# Sheet1.net
KiCad netlist of a schematic drawn in Altium Designer
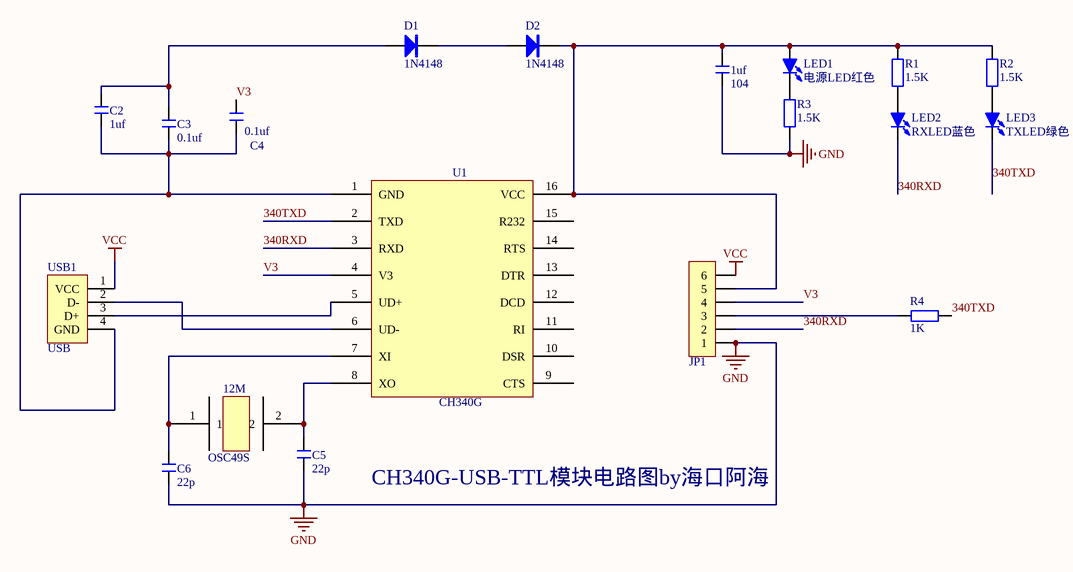
[diagram p0: Sheet1.SchDoc]

(export (version "E")
  (design (tool "Eeschema 10.0.6"))
  (components
    (comp (ref "1uf")
      (value "104")
      (footprint "C 0603_L")
      (description "贴片电容")
      (libsource (lib "0.1 - 电阻-电容-电感") (part "C"))
    )
    (comp (ref "12M")
      (value "OSC49S")
      (footprint "OSC HC-49S")
      (description "晶振49S")
      (libsource (lib "常用元件库") (part "OSC49S"))
    )
    (comp (ref "C2")
      (value "1uf")
      (footprint "C 0603_L")
      (description "贴片电容")
      (libsource (lib "0.1 - 电阻-电容-电感") (part "C"))
    )
    (comp (ref "C3")
      (value "0.1uf")
      (footprint "C 0603_L")
      (description "贴片电容")
      (libsource (lib "0.1 - 电阻-电容-电感") (part "C"))
    )
    (comp (ref "C4")
      (value "0.1uf")
      (footprint "C 0603_L")
      (description "贴片电容")
      (libsource (lib "0.1 - 电阻-电容-电感") (part "C"))
    )
    (comp (ref "C5")
      (value "22p")
      (footprint "C 0603_L")
      (description "贴片电容")
      (libsource (lib "0.1 - 电阻-电容-电感") (part "C"))
    )
    (comp (ref "C6")
      (value "22p")
      (footprint "C 0603_L")
      (description "贴片电容")
      (libsource (lib "0.1 - 电阻-电容-电感") (part "C"))
    )
    (comp (ref "D1")
      (value "1N4148")
      (footprint "MINI_MELF (LL34)")
      (description "开关二极管")
      (libsource (lib "0.2 - 二极管-整流桥") (part "1N4148"))
    )
    (comp (ref "D2")
      (value "1N4148")
      (footprint "MINI_MELF (LL34)")
      (description "开关二极管")
      (libsource (lib "0.2 - 二极管-整流桥") (part "1N4148"))
    )
    (comp (ref "JP1")
      (value "HDR-1X6")
      (footprint "HDR2.54-LI-6P")
      (description "6P接插件")
      (fields (field (name "版权归属") "封装库来自淘宝 ID：黄晶宝石"))
      (libsource (lib "5.4 - 接插件-脚距2.54 (100mil) ") (part "Header 6"))
    )
    (comp (ref "LED1")
      (value "电源LED红色")
      (footprint "LED 0603R")
      (description "贴片LED")
      (fields (field (name "版权归属") "封装库来自淘宝 ID：黄晶宝石"))
      (libsource (lib "0.3 - LED发光二极管") (part "LED-SMD"))
    )
    (comp (ref "LED2")
      (value "RXLED蓝色")
      (footprint "LED 0603B")
      (description "贴片LED")
      (fields (field (name "版权归属") "封装库来自淘宝 ID：黄晶宝石"))
      (libsource (lib "0.3 - LED发光二极管") (part "LED-SMD"))
    )
    (comp (ref "LED3")
      (value "TXLED绿色")
      (footprint "LED 0603G")
      (description "贴片LED")
      (fields (field (name "版权归属") "封装库来自淘宝 ID：黄晶宝石"))
      (libsource (lib "0.3 - LED发光二极管") (part "LED-SMD"))
    )
    (comp (ref "R1")
      (value "1.5K")
      (footprint "R 0603_L")
      (description "贴片电阻")
      (fields (field (name "版权归属") "来自淘宝 ID：黄晶宝石"))
      (libsource (lib "0.1 - 电阻-电容-电感") (part "R"))
    )
    (comp (ref "R2")
      (value "1.5K")
      (footprint "R 0603_L")
      (description "贴片电阻")
      (fields (field (name "版权归属") "来自淘宝 ID：黄晶宝石"))
      (libsource (lib "0.1 - 电阻-电容-电感") (part "R"))
    )
    (comp (ref "R3")
      (value "1.5K")
      (footprint "R 0603_L")
      (description "贴片电阻")
      (fields (field (name "版权归属") "来自淘宝 ID：黄晶宝石"))
      (libsource (lib "0.1 - 电阻-电容-电感") (part "R"))
    )
    (comp (ref "R4")
      (value "1K")
      (footprint "R 0603_L")
      (description "贴片电阻")
      (fields (field (name "版权归属") "来自淘宝 ID：黄晶宝石"))
      (libsource (lib "0.1 - 电阻-电容-电感") (part "R"))
    )
    (comp (ref "U1")
      (value "CH340G")
      (footprint "SOP16")
      (description "USB总线转接芯片")
      (libsource (lib "常用元件库") (part "CH340G"))
    )
    (comp (ref "USB1")
      (value "USB")
      (footprint "USB_A/P_A")
      (description "USB-A型公接口")
      (fields (field (name "版权归属") "封装库来自淘宝卖家 ID：黄晶宝石"))
      (libsource (lib "0.8 - 以太网-音频-USB插座") (part "USB-A/P"))
    )
  )
  (nets
    (net (code "1") (name "/340RXD") (class "Default")
      (node (ref "JP1") (pin "2") (pinfunction "2_2") (pintype "passive"))
      (node (ref "LED2") (pin "2") (pinfunction "K_2") (pintype "passive"))
      (node (ref "U1") (pin "3") (pinfunction "RXD_3") (pintype "passive"))
    )
    (net (code "2") (name "/340TXD") (class "Default")
      (node (ref "LED3") (pin "2") (pinfunction "K_2") (pintype "passive"))
      (node (ref "R4") (pin "2") (pinfunction "2_2") (pintype "passive"))
      (node (ref "U1") (pin "2") (pinfunction "TXD_2") (pintype "passive"))
    )
    (net (code "3") (name "/V3") (class "Default")
      (node (ref "C4") (pin "2") (pinfunction "2_2") (pintype "passive"))
      (node (ref "JP1") (pin "4") (pinfunction "4_4") (pintype "passive"))
      (node (ref "U1") (pin "4") (pinfunction "V3_4") (pintype "passive"))
    )
    (net (code "4") (name "GND") (class "Default")
      (node (ref "1uf") (pin "2") (pinfunction "2_2") (pintype "passive"))
      (node (ref "C5") (pin "1") (pinfunction "1_1") (pintype "passive"))
      (node (ref "C6") (pin "1") (pinfunction "1_1") (pintype "passive"))
      (node (ref "JP1") (pin "1") (pinfunction "1_1") (pintype "passive"))
      (node (ref "R3") (pin "1") (pinfunction "1_1") (pintype "passive"))
    )
    (net (code "5") (name "Net-(D1-A)") (class "Default")
      (node (ref "C2") (pin "2") (pinfunction "2_2") (pintype "passive"))
      (node (ref "C3") (pin "2") (pinfunction "2_2") (pintype "passive"))
      (node (ref "D1") (pin "1") (pinfunction "A_1") (pintype "passive"))
    )
    (net (code "6") (name "Net-(D1-K)") (class "Default")
      (node (ref "D1") (pin "2") (pinfunction "K_2") (pintype "passive"))
      (node (ref "D2") (pin "1") (pinfunction "A_1") (pintype "passive"))
    )
    (net (code "7") (name "Net-(D2-K)") (class "Default")
      (node (ref "1uf") (pin "1") (pinfunction "1_1") (pintype "passive"))
      (node (ref "D2") (pin "2") (pinfunction "K_2") (pintype "passive"))
      (node (ref "JP1") (pin "5") (pinfunction "5_5") (pintype "passive"))
      (node (ref "LED1") (pin "1") (pinfunction "A_1") (pintype "passive"))
      (node (ref "R1") (pin "2") (pinfunction "2_2") (pintype "passive"))
      (node (ref "R2") (pin "2") (pinfunction "2_2") (pintype "passive"))
      (node (ref "U1") (pin "16") (pinfunction "VCC_16") (pintype "passive"))
    )
    (net (code "8") (name "Net-(JP1-Pad3)") (class "Default")
      (node (ref "JP1") (pin "3") (pinfunction "3_3") (pintype "passive"))
      (node (ref "R4") (pin "1") (pinfunction "1_1") (pintype "passive"))
    )
    (net (code "9") (name "Net-(LED1-K)") (class "Default")
      (node (ref "LED1") (pin "2") (pinfunction "K_2") (pintype "passive"))
      (node (ref "R3") (pin "2") (pinfunction "2_2") (pintype "passive"))
    )
    (net (code "10") (name "Net-(LED2-A)") (class "Default")
      (node (ref "LED2") (pin "1") (pinfunction "A_1") (pintype "passive"))
      (node (ref "R1") (pin "1") (pinfunction "1_1") (pintype "passive"))
    )
    (net (code "11") (name "Net-(LED3-A)") (class "Default")
      (node (ref "LED3") (pin "1") (pinfunction "A_1") (pintype "passive"))
      (node (ref "R2") (pin "1") (pinfunction "1_1") (pintype "passive"))
    )
    (net (code "12") (name "Net-(U1-GND)") (class "Default")
      (node (ref "C2") (pin "1") (pinfunction "1_1") (pintype "passive"))
      (node (ref "C3") (pin "1") (pinfunction "1_1") (pintype "passive"))
      (node (ref "C4") (pin "1") (pinfunction "1_1") (pintype "passive"))
      (node (ref "U1") (pin "1") (pinfunction "GND_1") (pintype "passive"))
      (node (ref "USB1") (pin "4") (pinfunction "GND_4") (pintype "passive"))
    )
    (net (code "13") (name "Net-(U1-UD+)") (class "Default")
      (node (ref "U1") (pin "5") (pinfunction "UD+_5") (pintype "passive"))
      (node (ref "USB1") (pin "3") (pinfunction "D+_3") (pintype "passive"))
    )
    (net (code "14") (name "Net-(U1-UD-)") (class "Default")
      (node (ref "U1") (pin "6") (pinfunction "UD-_6") (pintype "passive"))
      (node (ref "USB1") (pin "2") (pinfunction "D-_2") (pintype "passive"))
    )
    (net (code "15") (name "Net-(U1-XI)") (class "Default")
      (node (ref "12M") (pin "1") (pinfunction "1_1") (pintype "passive"))
      (node (ref "C6") (pin "2") (pinfunction "2_2") (pintype "passive"))
      (node (ref "U1") (pin "7") (pinfunction "XI_7") (pintype "passive"))
    )
    (net (code "16") (name "Net-(U1-XO)") (class "Default")
      (node (ref "12M") (pin "2") (pinfunction "2_2") (pintype "passive"))
      (node (ref "C5") (pin "2") (pinfunction "2_2") (pintype "passive"))
      (node (ref "U1") (pin "8") (pinfunction "XO_8") (pintype "passive"))
    )
    (net (code "17") (name "VCC") (class "Default")
      (node (ref "JP1") (pin "6") (pinfunction "6_6") (pintype "passive"))
      (node (ref "USB1") (pin "1") (pinfunction "VCC_1") (pintype "passive"))
    )
    (net (code "18") (name "unconnected-(U1-CTS-Pad9)") (class "Default")
      (node (ref "U1") (pin "9") (pinfunction "CTS_9") (pintype "passive"))
    )
    (net (code "19") (name "unconnected-(U1-DCD-Pad12)") (class "Default")
      (node (ref "U1") (pin "12") (pinfunction "DCD_12") (pintype "passive"))
    )
    (net (code "20") (name "unconnected-(U1-DSR-Pad10)") (class "Default")
      (node (ref "U1") (pin "10") (pinfunction "DSR_10") (pintype "passive"))
    )
    (net (code "21") (name "unconnected-(U1-DTR-Pad13)") (class "Default")
      (node (ref "U1") (pin "13") (pinfunction "DTR_13") (pintype "passive"))
    )
    (net (code "22") (name "unconnected-(U1-R232-Pad15)") (class "Default")
      (node (ref "U1") (pin "15") (pinfunction "R232_15") (pintype "passive"))
    )
    (net (code "23") (name "unconnected-(U1-RI-Pad11)") (class "Default")
      (node (ref "U1") (pin "11") (pinfunction "RI_11") (pintype "passive"))
    )
    (net (code "24") (name "unconnected-(U1-RTS-Pad14)") (class "Default")
      (node (ref "U1") (pin "14") (pinfunction "RTS_14") (pintype "passive"))
    )
  )
)
